# weather_station_-_simple.net
KiCad netlist of a schematic drawn in EAGLE
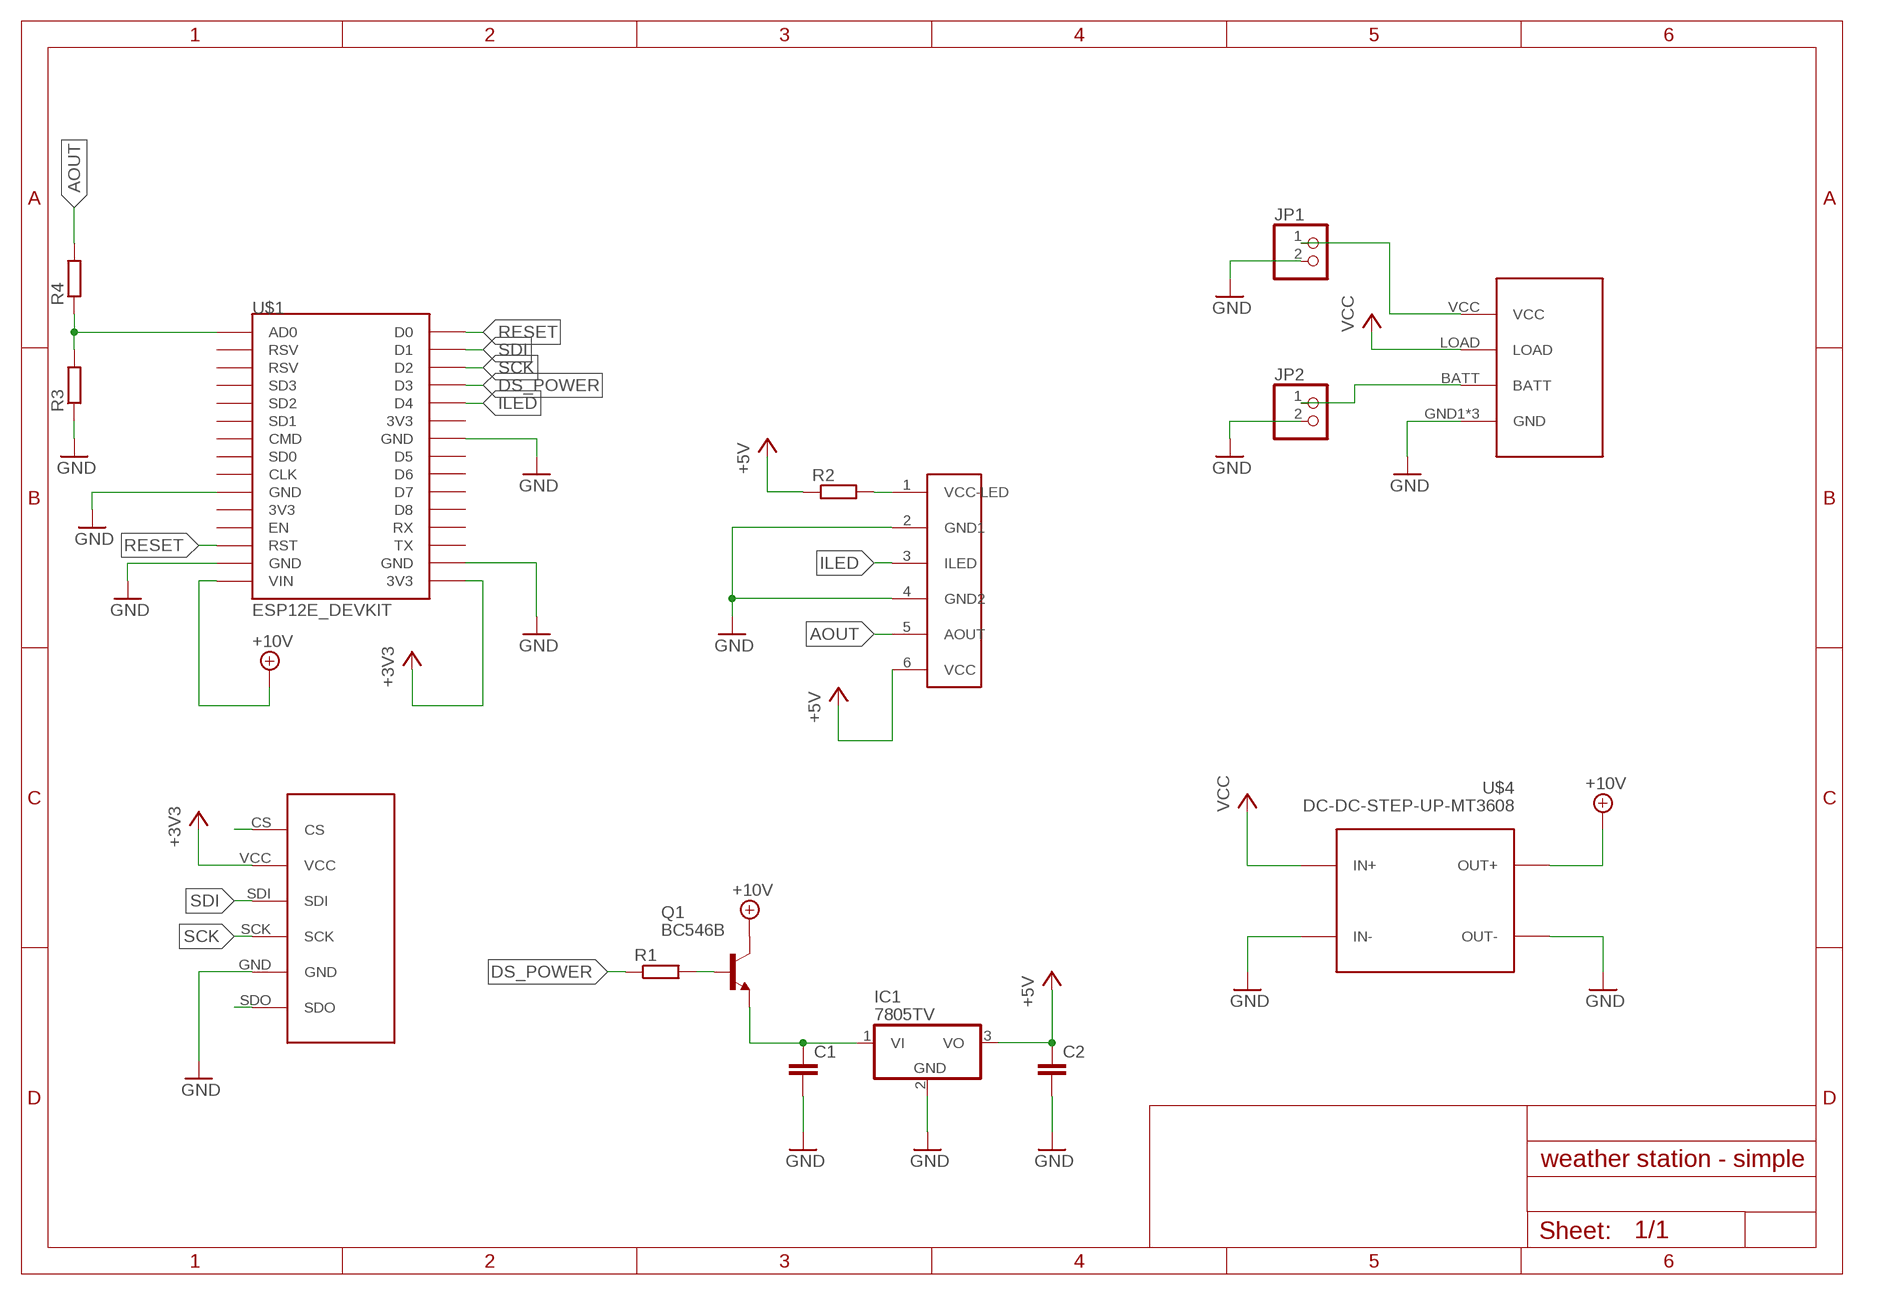
[diagram p0: schematic, sheet 1]

(export (version "E")
  (design (tool "Eeschema 10.0.6"))
  (components
    (comp (ref "C1")
      (value "C-EU025-024X044")
      (footprint "eagle-import:C025-024X044")
      (libsource (lib "eagle-import") (part "C-EU025-024X044"))
    )
    (comp (ref "C2")
      (value "C-EU025-024X044")
      (footprint "eagle-import:C025-024X044")
      (libsource (lib "eagle-import") (part "C-EU025-024X044"))
    )
    (comp (ref "IC1")
      (value "7805TV")
      (footprint "eagle-import:TO220V")
      (libsource (lib "eagle-import") (part "78TV05"))
    )
    (comp (ref "JP1")
      (value "PINHD-1X2")
      (footprint "eagle-import:1X02")
      (libsource (lib "eagle-import") (part "PINHD-1X2"))
    )
    (comp (ref "JP2")
      (value "PINHD-1X2")
      (footprint "eagle-import:1X02")
      (libsource (lib "eagle-import") (part "PINHD-1X2"))
    )
    (comp (ref "Q1")
      (value "BC546B")
      (footprint "eagle-import:TO92-EBC")
      (libsource (lib "eagle-import") (part "BC546B"))
    )
    (comp (ref "R1")
      (value "R-EU_0207/10")
      (footprint "eagle-import:0207_10")
      (libsource (lib "eagle-import") (part "R-EU_0207/10"))
    )
    (comp (ref "R2")
      (value "R-EU_0207/10")
      (footprint "eagle-import:0207_10")
      (libsource (lib "eagle-import") (part "R-EU_0207/10"))
    )
    (comp (ref "R3")
      (value "R-EU_0207/10")
      (footprint "eagle-import:0207_10")
      (libsource (lib "eagle-import") (part "R-EU_0207/10"))
    )
    (comp (ref "R4")
      (value "R-EU_0207/10")
      (footprint "eagle-import:0207_10")
      (libsource (lib "eagle-import") (part "R-EU_0207/10"))
    )
    (comp (ref "U$1")
      (value "ESP12E_DEVKIT")
      (footprint "eagle-import:ESP12E_DEVKIT")
      (libsource (lib "eagle-import") (part "ESP12E_DEVKIT"))
    )
    (comp (ref "U$2")
      (value "ADAFRUIT_SOLARCHARGER")
      (footprint "eagle-import:ADAFRUIT_SOLARCHARGER")
      (libsource (lib "eagle-import") (part "ADAFRUIT_SOLARCHARGER"))
    )
    (comp (ref "U$3")
      (value "BME680_BLUEDOT")
      (footprint "eagle-import:1X06")
      (libsource (lib "eagle-import") (part "BME680_BLUEDOT"))
    )
    (comp (ref "U$4")
      (value "DC-DC-STEP-UP-MT3608")
      (footprint "eagle-import:DC-DC-STEP-UP-MT3608")
      (libsource (lib "eagle-import") (part "DC-DC-STEP-UP-MT3608"))
    )
    (comp (ref "U$5")
      (value "DUST_SENSOR")
      (footprint "eagle-import:DUST_SENSOR")
      (libsource (lib "eagle-import") (part "DUST_SENSOR"))
    )
  )
  (nets
    (net (code "1") (name "+3V3") (class "Default")
      (node (ref "U$1") (pin "3V3@2") (pinfunction "3V3_3V3@2") (pintype "bidirectional"))
      (node (ref "U$3") (pin "VCC") (pinfunction "VCC_VCC") (pintype "bidirectional"))
    )
    (net (code "2") (name "+5V") (class "Default")
      (node (ref "C2") (pin "1") (pinfunction "1_1") (pintype "passive"))
      (node (ref "IC1") (pin "3") (pinfunction "VO_3") (pintype "passive"))
      (node (ref "R2") (pin "1") (pinfunction "1_1") (pintype "passive"))
      (node (ref "U$5") (pin "6") (pinfunction "VCC_6") (pintype "power_in"))
    )
    (net (code "3") (name "+10V") (class "Default")
      (node (ref "Q1") (pin "C") (pinfunction "C_C") (pintype "passive"))
      (node (ref "U$1") (pin "VIN") (pinfunction "VIN_VIN") (pintype "bidirectional"))
      (node (ref "U$4") (pin "OUT+") (pinfunction "OUT+_OUT+") (pintype "bidirectional"))
    )
    (net (code "4") (name "AOUT") (class "Default")
      (node (ref "R4") (pin "2") (pinfunction "2_2") (pintype "passive"))
      (node (ref "U$5") (pin "5") (pinfunction "AOUT_5") (pintype "output"))
    )
    (net (code "5") (name "DS_POWER") (class "Default")
      (node (ref "R1") (pin "1") (pinfunction "1_1") (pintype "passive"))
      (node (ref "U$1") (pin "D3") (pinfunction "D3_D3") (pintype "bidirectional"))
    )
    (net (code "6") (name "GND") (class "Default")
      (node (ref "C1") (pin "2") (pinfunction "2_2") (pintype "passive"))
      (node (ref "C2") (pin "2") (pinfunction "2_2") (pintype "passive"))
      (node (ref "IC1") (pin "2") (pinfunction "GND_2") (pintype "passive"))
      (node (ref "JP1") (pin "2") (pinfunction "2_2") (pintype "passive"))
      (node (ref "JP2") (pin "2") (pinfunction "2_2") (pintype "passive"))
      (node (ref "R3") (pin "1") (pinfunction "1_1") (pintype "passive"))
      (node (ref "U$1") (pin "GND@0") (pinfunction "GND_GND@0") (pintype "bidirectional"))
      (node (ref "U$1") (pin "GND@1") (pinfunction "GND_GND@1") (pintype "bidirectional"))
      (node (ref "U$1") (pin "GND@2") (pinfunction "GND_GND@2") (pintype "bidirectional"))
      (node (ref "U$1") (pin "GND@3") (pinfunction "GND_GND@3") (pintype "bidirectional"))
      (node (ref "U$2") (pin "GND1") (pinfunction "GND_GND1") (pintype "power_in"))
      (node (ref "U$2") (pin "GND2") (pinfunction "GND_GND2") (pintype "power_in"))
      (node (ref "U$2") (pin "GND3") (pinfunction "GND_GND3") (pintype "power_in"))
      (node (ref "U$3") (pin "GND") (pinfunction "GND_GND") (pintype "bidirectional"))
      (node (ref "U$4") (pin "IN-") (pinfunction "IN-_IN-") (pintype "bidirectional"))
      (node (ref "U$4") (pin "OUT-") (pinfunction "OUT-_OUT-") (pintype "bidirectional"))
      (node (ref "U$5") (pin "2") (pinfunction "GND1_2") (pintype "power_in"))
      (node (ref "U$5") (pin "4") (pinfunction "GND2_4") (pintype "power_in"))
    )
    (net (code "7") (name "ILED") (class "Default")
      (node (ref "U$1") (pin "D4") (pinfunction "D4_D4") (pintype "bidirectional"))
      (node (ref "U$5") (pin "3") (pinfunction "ILED_3") (pintype "input"))
    )
    (net (code "8") (name "Net-(IC1-VI)") (class "Default")
      (node (ref "C1") (pin "1") (pinfunction "1_1") (pintype "passive"))
      (node (ref "IC1") (pin "1") (pinfunction "VI_1") (pintype "input"))
      (node (ref "Q1") (pin "E") (pinfunction "E_E") (pintype "passive"))
    )
    (net (code "9") (name "Net-(JP1-Pad1)") (class "Default")
      (node (ref "JP1") (pin "1") (pinfunction "1_1") (pintype "passive"))
      (node (ref "U$2") (pin "VCC") (pinfunction "VCC_VCC") (pintype "power_in"))
    )
    (net (code "10") (name "Net-(JP2-Pad1)") (class "Default")
      (node (ref "JP2") (pin "1") (pinfunction "1_1") (pintype "passive"))
      (node (ref "U$2") (pin "BATT") (pinfunction "BATT_BATT") (pintype "output"))
    )
    (net (code "11") (name "Net-(Q1-PadB)") (class "Default")
      (node (ref "Q1") (pin "B") (pinfunction "B_B") (pintype "passive"))
      (node (ref "R1") (pin "2") (pinfunction "2_2") (pintype "passive"))
    )
    (net (code "12") (name "Net-(R3-Pad2)") (class "Default")
      (node (ref "R3") (pin "2") (pinfunction "2_2") (pintype "passive"))
      (node (ref "R4") (pin "1") (pinfunction "1_1") (pintype "passive"))
      (node (ref "U$1") (pin "AD0") (pinfunction "AD0_AD0") (pintype "bidirectional"))
    )
    (net (code "13") (name "Net-(U$5-VCC-LED)") (class "Default")
      (node (ref "R2") (pin "2") (pinfunction "2_2") (pintype "passive"))
      (node (ref "U$5") (pin "1") (pinfunction "VCC-LED_1") (pintype "power_in"))
    )
    (net (code "14") (name "RESET") (class "Default")
      (node (ref "U$1") (pin "D0") (pinfunction "D0_D0") (pintype "bidirectional"))
      (node (ref "U$1") (pin "RST") (pinfunction "RST_RST") (pintype "bidirectional"))
    )
    (net (code "15") (name "SCK") (class "Default")
      (node (ref "U$1") (pin "D2") (pinfunction "D2_D2") (pintype "bidirectional"))
      (node (ref "U$3") (pin "SCK") (pinfunction "SCK_SCK") (pintype "bidirectional"))
    )
    (net (code "16") (name "SDI") (class "Default")
      (node (ref "U$1") (pin "D1") (pinfunction "D1_D1") (pintype "bidirectional"))
      (node (ref "U$3") (pin "SDI") (pinfunction "SDI_SDI") (pintype "bidirectional"))
    )
    (net (code "17") (name "VCC") (class "Default")
      (node (ref "U$2") (pin "LOAD") (pinfunction "LOAD_LOAD") (pintype "output"))
      (node (ref "U$4") (pin "IN+") (pinfunction "IN+_IN+") (pintype "bidirectional"))
    )
    (net (code "18") (name "unconnected-(U$1-3V3-Pad3V3@0)") (class "Default")
      (node (ref "U$1") (pin "3V3@0") (pinfunction "3V3_3V3@0") (pintype "bidirectional"))
    )
    (net (code "19") (name "unconnected-(U$1-3V3-Pad3V3@1)") (class "Default")
      (node (ref "U$1") (pin "3V3@1") (pinfunction "3V3_3V3@1") (pintype "bidirectional"))
    )
    (net (code "20") (name "unconnected-(U$1-PadCLK)") (class "Default")
      (node (ref "U$1") (pin "CLK") (pinfunction "CLK_CLK") (pintype "bidirectional"))
    )
    (net (code "21") (name "unconnected-(U$1-PadCMD)") (class "Default")
      (node (ref "U$1") (pin "CMD") (pinfunction "CMD_CMD") (pintype "bidirectional"))
    )
    (net (code "22") (name "unconnected-(U$1-PadD5)") (class "Default")
      (node (ref "U$1") (pin "D5") (pinfunction "D5_D5") (pintype "bidirectional"))
    )
    (net (code "23") (name "unconnected-(U$1-PadD6)") (class "Default")
      (node (ref "U$1") (pin "D6") (pinfunction "D6_D6") (pintype "bidirectional"))
    )
    (net (code "24") (name "unconnected-(U$1-PadD7)") (class "Default")
      (node (ref "U$1") (pin "D7") (pinfunction "D7_D7") (pintype "bidirectional"))
    )
    (net (code "25") (name "unconnected-(U$1-PadD8)") (class "Default")
      (node (ref "U$1") (pin "D8") (pinfunction "D8_D8") (pintype "bidirectional"))
    )
    (net (code "26") (name "unconnected-(U$1-PadEN)") (class "Default")
      (node (ref "U$1") (pin "EN") (pinfunction "EN_EN") (pintype "bidirectional"))
    )
    (net (code "27") (name "unconnected-(U$1-PadRX)") (class "Default")
      (node (ref "U$1") (pin "RX") (pinfunction "RX_RX") (pintype "bidirectional"))
    )
    (net (code "28") (name "unconnected-(U$1-PadSD0)") (class "Default")
      (node (ref "U$1") (pin "SD0") (pinfunction "SD0_SD0") (pintype "bidirectional"))
    )
    (net (code "29") (name "unconnected-(U$1-PadSD1)") (class "Default")
      (node (ref "U$1") (pin "SD1") (pinfunction "SD1_SD1") (pintype "bidirectional"))
    )
    (net (code "30") (name "unconnected-(U$1-PadSD2)") (class "Default")
      (node (ref "U$1") (pin "SD2") (pinfunction "SD2_SD2") (pintype "bidirectional"))
    )
    (net (code "31") (name "unconnected-(U$1-PadSD3)") (class "Default")
      (node (ref "U$1") (pin "SD3") (pinfunction "SD3_SD3") (pintype "bidirectional"))
    )
    (net (code "32") (name "unconnected-(U$1-PadTX)") (class "Default")
      (node (ref "U$1") (pin "TX") (pinfunction "TX_TX") (pintype "bidirectional"))
    )
    (net (code "33") (name "unconnected-(U$1-RSV-PadRSV@0)") (class "Default")
      (node (ref "U$1") (pin "RSV@0") (pinfunction "RSV_RSV@0") (pintype "bidirectional"))
    )
    (net (code "34") (name "unconnected-(U$1-RSV-PadRSV@1)") (class "Default")
      (node (ref "U$1") (pin "RSV@1") (pinfunction "RSV_RSV@1") (pintype "bidirectional"))
    )
    (net (code "35") (name "unconnected-(U$3-PadCS)") (class "Default")
      (node (ref "U$3") (pin "CS") (pinfunction "CS_CS") (pintype "bidirectional"))
    )
    (net (code "36") (name "unconnected-(U$3-PadSDO)") (class "Default")
      (node (ref "U$3") (pin "SDO") (pinfunction "SDO_SDO") (pintype "bidirectional"))
    )
  )
)
